# schema.net
KiCad netlist of a schematic drawn in EAGLE
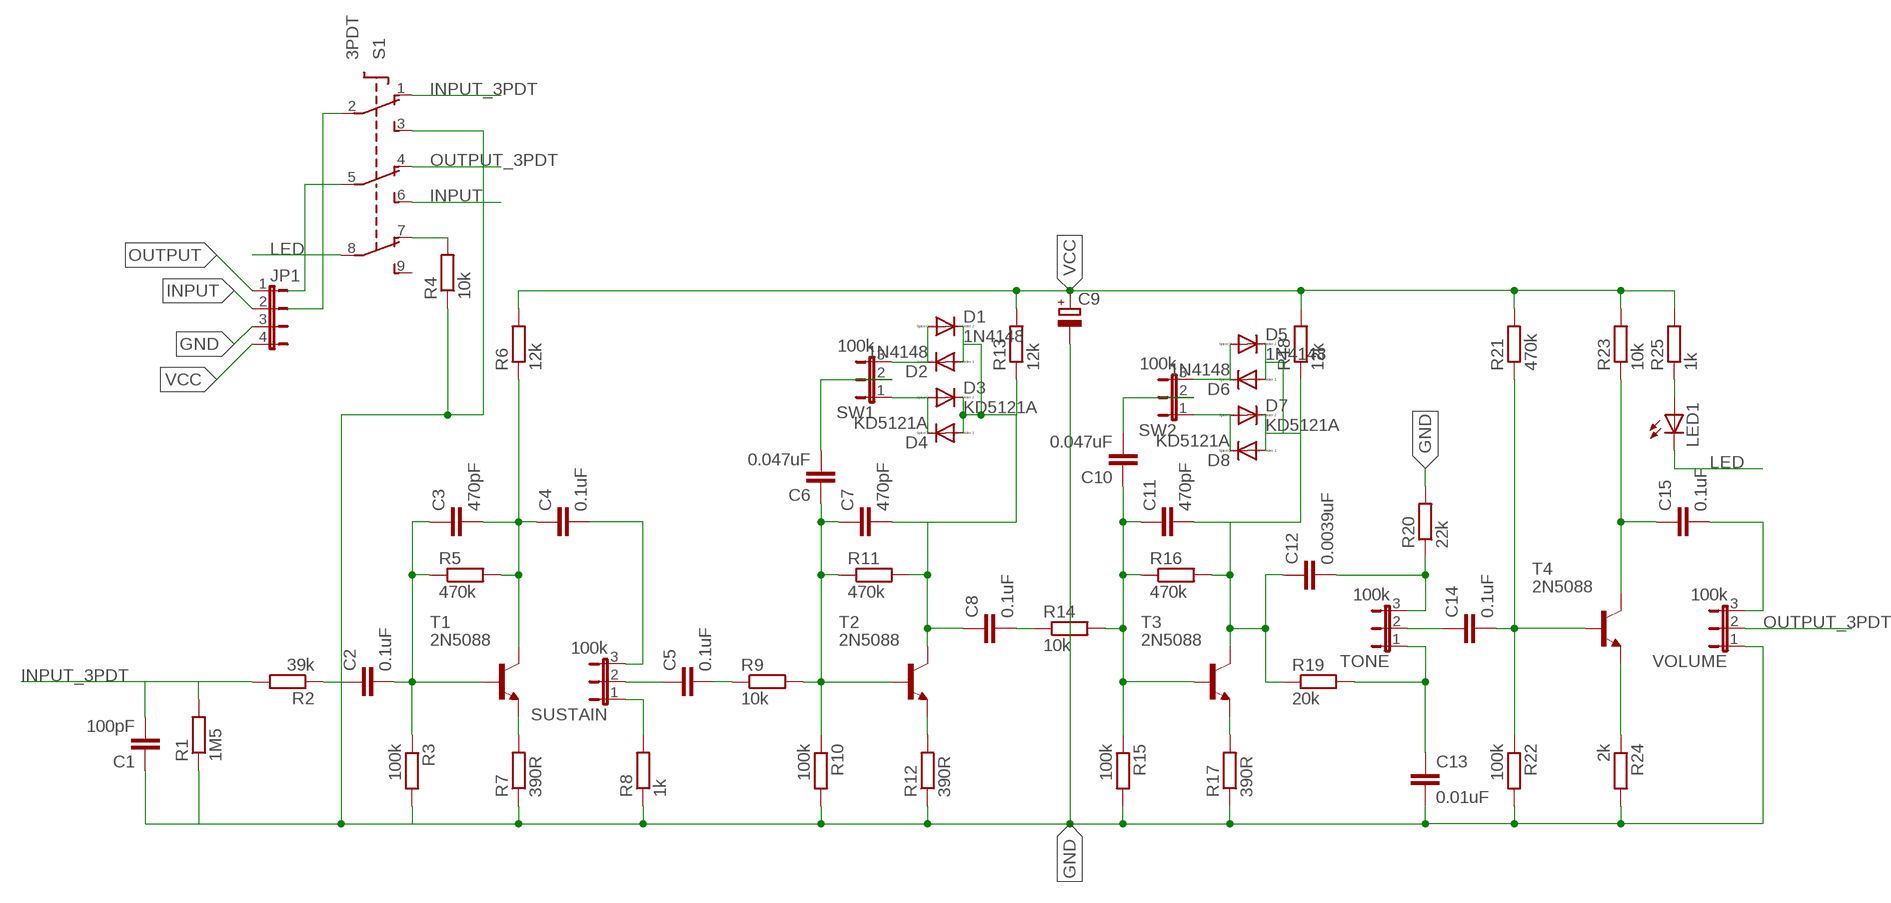
[diagram p0: schematic, sheet 1]

(export (version "E")
  (design (tool "Eeschema 10.0.6"))
  (components
    (comp (ref "C1")
      (value "100pF")
      (footprint "eagle-import:C025-025X050")
      (libsource (lib "eagle-import") (part "C-EU025-025X050"))
    )
    (comp (ref "C2")
      (value "0.1uF")
      (footprint "eagle-import:C075-042X103")
      (libsource (lib "eagle-import") (part "C-EU075-042X103"))
    )
    (comp (ref "C3")
      (value "470pF")
      (footprint "eagle-import:C025-025X050")
      (libsource (lib "eagle-import") (part "C-EU025-025X050"))
    )
    (comp (ref "C4")
      (value "0.1uF")
      (footprint "eagle-import:C075-042X103")
      (libsource (lib "eagle-import") (part "C-EU075-042X103"))
    )
    (comp (ref "C5")
      (value "0.1uF")
      (footprint "eagle-import:C075-042X103")
      (libsource (lib "eagle-import") (part "C-EU075-042X103"))
    )
    (comp (ref "C6")
      (value "0.047uF")
      (footprint "eagle-import:C102-043X133")
      (libsource (lib "eagle-import") (part "C-EU102-043X133"))
    )
    (comp (ref "C7")
      (value "470pF")
      (footprint "eagle-import:C025-025X050")
      (libsource (lib "eagle-import") (part "C-EU025-025X050"))
    )
    (comp (ref "C8")
      (value "0.1uF")
      (footprint "eagle-import:C075-042X103")
      (libsource (lib "eagle-import") (part "C-EU075-042X103"))
    )
    (comp (ref "C9")
      (value "CPOL-EUE2.5-6")
      (footprint "eagle-import:E2,5-6")
      (libsource (lib "eagle-import") (part "CPOL-EUE2.5-6"))
    )
    (comp (ref "C10")
      (value "0.047uF")
      (footprint "eagle-import:C102-043X133")
      (libsource (lib "eagle-import") (part "C-EU102-043X133"))
    )
    (comp (ref "C11")
      (value "470pF")
      (footprint "eagle-import:C025-025X050")
      (libsource (lib "eagle-import") (part "C-EU025-025X050"))
    )
    (comp (ref "C12")
      (value "0.0039uF")
      (footprint "eagle-import:C050-045X075")
      (libsource (lib "eagle-import") (part "C-EU050-045X075"))
    )
    (comp (ref "C13")
      (value "0.01uF")
      (footprint "eagle-import:C075-042X103")
      (libsource (lib "eagle-import") (part "C-EU075-042X103"))
    )
    (comp (ref "C14")
      (value "0.1uF")
      (footprint "eagle-import:C075-042X103")
      (libsource (lib "eagle-import") (part "C-EU075-042X103"))
    )
    (comp (ref "C15")
      (value "0.1uF")
      (footprint "eagle-import:C075-042X103")
      (libsource (lib "eagle-import") (part "C-EU075-042X103"))
    )
    (comp (ref "D1")
      (value "1N4148")
      (footprint "eagle-import:DO35-10")
      (libsource (lib "eagle-import") (part "1N4148DO35-10"))
    )
    (comp (ref "D2")
      (value "1N4148")
      (footprint "eagle-import:DO35-10")
      (libsource (lib "eagle-import") (part "1N4148DO35-10"))
    )
    (comp (ref "D3")
      (value "KD5121A")
      (footprint "eagle-import:DO35-10")
      (libsource (lib "eagle-import") (part "1N4148DO35-10"))
    )
    (comp (ref "D4")
      (value "KD5121A")
      (footprint "eagle-import:DO35-10")
      (libsource (lib "eagle-import") (part "1N4148DO35-10"))
    )
    (comp (ref "D5")
      (value "1N4148")
      (footprint "eagle-import:DO35-10")
      (libsource (lib "eagle-import") (part "1N4148DO35-10"))
    )
    (comp (ref "D6")
      (value "1N4148")
      (footprint "eagle-import:DO35-10")
      (libsource (lib "eagle-import") (part "1N4148DO35-10"))
    )
    (comp (ref "D7")
      (value "KD5121A")
      (footprint "eagle-import:DO35-10")
      (libsource (lib "eagle-import") (part "1N4148DO35-10"))
    )
    (comp (ref "D8")
      (value "KD5121A")
      (footprint "eagle-import:DO35-10")
      (libsource (lib "eagle-import") (part "1N4148DO35-10"))
    )
    (comp (ref "JP1")
      (value "JP4E")
      (footprint "eagle-import:JP4")
      (libsource (lib "eagle-import") (part "JP4E"))
    )
    (comp (ref "LED1")
      (value "LEDB155")
      (footprint "eagle-import:Q62902-B155")
      (libsource (lib "eagle-import") (part "LEDB155"))
    )
    (comp (ref "R1")
      (value "1M5")
      (footprint "eagle-import:0204V")
      (libsource (lib "eagle-import") (part "R-EU_0204/2V"))
    )
    (comp (ref "R2")
      (value "39k")
      (footprint "eagle-import:0204V")
      (libsource (lib "eagle-import") (part "R-EU_0204/2V"))
    )
    (comp (ref "R3")
      (value "100k")
      (footprint "eagle-import:0204V")
      (libsource (lib "eagle-import") (part "R-EU_0204/2V"))
    )
    (comp (ref "R4")
      (value "10k")
      (footprint "eagle-import:0204V")
      (libsource (lib "eagle-import") (part "R-EU_0204/2V"))
    )
    (comp (ref "R5")
      (value "470k")
      (footprint "eagle-import:0204V")
      (libsource (lib "eagle-import") (part "R-EU_0204/2V"))
    )
    (comp (ref "R6")
      (value "12k")
      (footprint "eagle-import:0204V")
      (libsource (lib "eagle-import") (part "R-EU_0204/2V"))
    )
    (comp (ref "R7")
      (value "390R")
      (footprint "eagle-import:0204V")
      (libsource (lib "eagle-import") (part "R-EU_0204/2V"))
    )
    (comp (ref "R8")
      (value "1k")
      (footprint "eagle-import:0204V")
      (libsource (lib "eagle-import") (part "R-EU_0204/2V"))
    )
    (comp (ref "R9")
      (value "10k")
      (footprint "eagle-import:0204V")
      (libsource (lib "eagle-import") (part "R-EU_0204/2V"))
    )
    (comp (ref "R10")
      (value "100k")
      (footprint "eagle-import:0204V")
      (libsource (lib "eagle-import") (part "R-EU_0204/2V"))
    )
    (comp (ref "R11")
      (value "470k")
      (footprint "eagle-import:0204V")
      (libsource (lib "eagle-import") (part "R-EU_0204/2V"))
    )
    (comp (ref "R12")
      (value "390R")
      (footprint "eagle-import:0204V")
      (libsource (lib "eagle-import") (part "R-EU_0204/2V"))
    )
    (comp (ref "R13")
      (value "12k")
      (footprint "eagle-import:0204V")
      (libsource (lib "eagle-import") (part "R-EU_0204/2V"))
    )
    (comp (ref "R14")
      (value "10k")
      (footprint "eagle-import:0204V")
      (libsource (lib "eagle-import") (part "R-EU_0204/2V"))
    )
    (comp (ref "R15")
      (value "100k")
      (footprint "eagle-import:0204V")
      (libsource (lib "eagle-import") (part "R-EU_0204/2V"))
    )
    (comp (ref "R16")
      (value "470k")
      (footprint "eagle-import:0204V")
      (libsource (lib "eagle-import") (part "R-EU_0204/2V"))
    )
    (comp (ref "R17")
      (value "390R")
      (footprint "eagle-import:0204V")
      (libsource (lib "eagle-import") (part "R-EU_0204/2V"))
    )
    (comp (ref "R18")
      (value "12k")
      (footprint "eagle-import:0204V")
      (libsource (lib "eagle-import") (part "R-EU_0204/2V"))
    )
    (comp (ref "R19")
      (value "20k")
      (footprint "eagle-import:0204V")
      (libsource (lib "eagle-import") (part "R-EU_0204/2V"))
    )
    (comp (ref "R20")
      (value "22k")
      (footprint "eagle-import:0204V")
      (libsource (lib "eagle-import") (part "R-EU_0204/2V"))
    )
    (comp (ref "R21")
      (value "470k")
      (footprint "eagle-import:0204V")
      (libsource (lib "eagle-import") (part "R-EU_0204/2V"))
    )
    (comp (ref "R22")
      (value "100k")
      (footprint "eagle-import:0204V")
      (libsource (lib "eagle-import") (part "R-EU_0204/2V"))
    )
    (comp (ref "R23")
      (value "10k")
      (footprint "eagle-import:0204V")
      (libsource (lib "eagle-import") (part "R-EU_0204/2V"))
    )
    (comp (ref "R24")
      (value "2k")
      (footprint "eagle-import:0204V")
      (libsource (lib "eagle-import") (part "R-EU_0204/2V"))
    )
    (comp (ref "R25")
      (value "1k")
      (footprint "eagle-import:0204V")
      (libsource (lib "eagle-import") (part "R-EU_0204/2V"))
    )
    (comp (ref "S1")
      (value "3PDT")
      (footprint "eagle-import:3PDT")
      (libsource (lib "eagle-import") (part "3PDT"))
    )
    (comp (ref "SUSTAIN")
      (value "100k")
      (footprint "eagle-import:JP2")
      (libsource (lib "eagle-import") (part "JP2E"))
    )
    (comp (ref "SW1")
      (value "100k")
      (footprint "eagle-import:JP2")
      (libsource (lib "eagle-import") (part "JP2E"))
    )
    (comp (ref "SW2")
      (value "100k")
      (footprint "eagle-import:JP2")
      (libsource (lib "eagle-import") (part "JP2E"))
    )
    (comp (ref "T1")
      (value "2N5088")
      (footprint "eagle-import:TO92")
      (libsource (lib "eagle-import") (part "2N5088"))
    )
    (comp (ref "T2")
      (value "2N5088")
      (footprint "eagle-import:TO92")
      (libsource (lib "eagle-import") (part "2N5088"))
    )
    (comp (ref "T3")
      (value "2N5088")
      (footprint "eagle-import:TO92")
      (libsource (lib "eagle-import") (part "2N5088"))
    )
    (comp (ref "T4")
      (value "2N5088")
      (footprint "eagle-import:TO92")
      (libsource (lib "eagle-import") (part "2N5088"))
    )
    (comp (ref "TONE")
      (value "100k")
      (footprint "eagle-import:JP2")
      (libsource (lib "eagle-import") (part "JP2E"))
    )
    (comp (ref "VOLUME")
      (value "100k")
      (footprint "eagle-import:JP2")
      (libsource (lib "eagle-import") (part "JP2E"))
    )
  )
  (nets
    (net (code "1") (name "/INPUT_3PDT") (class "Default")
      (node (ref "C1") (pin "2") (pinfunction "2_2") (pintype "passive"))
      (node (ref "R1") (pin "2") (pinfunction "2_2") (pintype "passive"))
      (node (ref "R2") (pin "2") (pinfunction "2_2") (pintype "passive"))
      (node (ref "S1") (pin "1") (pinfunction "O1_1") (pintype "passive"))
    )
    (net (code "2") (name "/LED") (class "Default")
      (node (ref "LED1") (pin "K") (pinfunction "C_K") (pintype "passive"))
      (node (ref "S1") (pin "8") (pinfunction "P3_8") (pintype "passive"))
    )
    (net (code "3") (name "/OUTPUT_3PDT") (class "Default")
      (node (ref "S1") (pin "4") (pinfunction "O2_4") (pintype "passive"))
      (node (ref "VOLUME") (pin "2") (pinfunction "2_2") (pintype "passive"))
    )
    (net (code "4") (name "GND") (class "Default")
      (node (ref "C1") (pin "1") (pinfunction "1_1") (pintype "passive"))
      (node (ref "C13") (pin "2") (pinfunction "2_2") (pintype "passive"))
      (node (ref "C9") (pin "-") (pinfunction "-_-") (pintype "passive"))
      (node (ref "JP1") (pin "3") (pinfunction "3_3") (pintype "passive"))
      (node (ref "R1") (pin "1") (pinfunction "1_1") (pintype "passive"))
      (node (ref "R10") (pin "2") (pinfunction "2_2") (pintype "passive"))
      (node (ref "R12") (pin "1") (pinfunction "1_1") (pintype "passive"))
      (node (ref "R15") (pin "2") (pinfunction "2_2") (pintype "passive"))
      (node (ref "R17") (pin "1") (pinfunction "1_1") (pintype "passive"))
      (node (ref "R20") (pin "2") (pinfunction "2_2") (pintype "passive"))
      (node (ref "R22") (pin "2") (pinfunction "2_2") (pintype "passive"))
      (node (ref "R24") (pin "2") (pinfunction "2_2") (pintype "passive"))
      (node (ref "R3") (pin "2") (pinfunction "2_2") (pintype "passive"))
      (node (ref "R4") (pin "1") (pinfunction "1_1") (pintype "passive"))
      (node (ref "R7") (pin "1") (pinfunction "1_1") (pintype "passive"))
      (node (ref "R8") (pin "1") (pinfunction "1_1") (pintype "passive"))
      (node (ref "S1") (pin "3") (pinfunction "S1_3") (pintype "passive"))
      (node (ref "VOLUME") (pin "1") (pinfunction "1_1") (pintype "passive"))
    )
    (net (code "5") (name "INPUT") (class "Default")
      (node (ref "JP1") (pin "2") (pinfunction "2_2") (pintype "passive"))
      (node (ref "S1") (pin "6") (pinfunction "S2_6") (pintype "passive"))
    )
    (net (code "6") (name "Net-(C2-Pad1)") (class "Default")
      (node (ref "C2") (pin "1") (pinfunction "1_1") (pintype "passive"))
      (node (ref "R2") (pin "1") (pinfunction "1_1") (pintype "passive"))
    )
    (net (code "7") (name "Net-(C4-Pad2)") (class "Default")
      (node (ref "C4") (pin "2") (pinfunction "2_2") (pintype "passive"))
      (node (ref "SUSTAIN") (pin "3") (pinfunction "3_3") (pintype "passive"))
    )
    (net (code "8") (name "Net-(C5-Pad1)") (class "Default")
      (node (ref "C5") (pin "1") (pinfunction "1_1") (pintype "passive"))
      (node (ref "SUSTAIN") (pin "2") (pinfunction "2_2") (pintype "passive"))
    )
    (net (code "9") (name "Net-(C5-Pad2)") (class "Default")
      (node (ref "C5") (pin "2") (pinfunction "2_2") (pintype "passive"))
      (node (ref "R9") (pin "1") (pinfunction "1_1") (pintype "passive"))
    )
    (net (code "10") (name "Net-(C6-Pad2)") (class "Default")
      (node (ref "C6") (pin "2") (pinfunction "2_2") (pintype "passive"))
      (node (ref "SW1") (pin "2") (pinfunction "2_2") (pintype "passive"))
    )
    (net (code "11") (name "Net-(C8-Pad2)") (class "Default")
      (node (ref "C8") (pin "2") (pinfunction "2_2") (pintype "passive"))
      (node (ref "R14") (pin "1") (pinfunction "1_1") (pintype "passive"))
    )
    (net (code "12") (name "Net-(C10-Pad2)") (class "Default")
      (node (ref "C10") (pin "2") (pinfunction "2_2") (pintype "passive"))
      (node (ref "SW2") (pin "2") (pinfunction "2_2") (pintype "passive"))
    )
    (net (code "13") (name "Net-(C12-Pad2)") (class "Default")
      (node (ref "C12") (pin "2") (pinfunction "2_2") (pintype "passive"))
      (node (ref "R20") (pin "1") (pinfunction "1_1") (pintype "passive"))
      (node (ref "TONE") (pin "3") (pinfunction "3_3") (pintype "passive"))
    )
    (net (code "14") (name "Net-(C13-Pad1)") (class "Default")
      (node (ref "C13") (pin "1") (pinfunction "1_1") (pintype "passive"))
      (node (ref "R19") (pin "2") (pinfunction "2_2") (pintype "passive"))
      (node (ref "TONE") (pin "1") (pinfunction "1_1") (pintype "passive"))
    )
    (net (code "15") (name "Net-(C14-Pad1)") (class "Default")
      (node (ref "C14") (pin "1") (pinfunction "1_1") (pintype "passive"))
      (node (ref "TONE") (pin "2") (pinfunction "2_2") (pintype "passive"))
    )
    (net (code "16") (name "Net-(C15-Pad2)") (class "Default")
      (node (ref "C15") (pin "2") (pinfunction "2_2") (pintype "passive"))
      (node (ref "VOLUME") (pin "3") (pinfunction "3_3") (pintype "passive"))
    )
    (net (code "17") (name "Net-(D1-PadA)") (class "Default")
      (node (ref "D1") (pin "A") (pinfunction "A_A") (pintype "passive"))
      (node (ref "D2") (pin "C") (pinfunction "C_C") (pintype "passive"))
      (node (ref "SW1") (pin "3") (pinfunction "3_3") (pintype "passive"))
    )
    (net (code "18") (name "Net-(D3-PadA)") (class "Default")
      (node (ref "D3") (pin "A") (pinfunction "A_A") (pintype "passive"))
      (node (ref "D4") (pin "C") (pinfunction "C_C") (pintype "passive"))
      (node (ref "SW1") (pin "1") (pinfunction "1_1") (pintype "passive"))
    )
    (net (code "19") (name "Net-(D5-PadA)") (class "Default")
      (node (ref "D5") (pin "A") (pinfunction "A_A") (pintype "passive"))
      (node (ref "D6") (pin "C") (pinfunction "C_C") (pintype "passive"))
      (node (ref "SW2") (pin "3") (pinfunction "3_3") (pintype "passive"))
    )
    (net (code "20") (name "Net-(D7-PadA)") (class "Default")
      (node (ref "D7") (pin "A") (pinfunction "A_A") (pintype "passive"))
      (node (ref "D8") (pin "C") (pinfunction "C_C") (pintype "passive"))
      (node (ref "SW2") (pin "1") (pinfunction "1_1") (pintype "passive"))
    )
    (net (code "21") (name "Net-(LED1-PadA)") (class "Default")
      (node (ref "LED1") (pin "A") (pinfunction "A_A") (pintype "passive"))
      (node (ref "R25") (pin "1") (pinfunction "1_1") (pintype "passive"))
    )
    (net (code "22") (name "Net-(R8-Pad2)") (class "Default")
      (node (ref "R8") (pin "2") (pinfunction "2_2") (pintype "passive"))
      (node (ref "SUSTAIN") (pin "1") (pinfunction "1_1") (pintype "passive"))
    )
    (net (code "23") (name "Net-(S1-O3)") (class "Default")
      (node (ref "R4") (pin "2") (pinfunction "2_2") (pintype "passive"))
      (node (ref "S1") (pin "7") (pinfunction "O3_7") (pintype "passive"))
    )
    (net (code "24") (name "Net-(T1-B)") (class "Default")
      (node (ref "C2") (pin "2") (pinfunction "2_2") (pintype "passive"))
      (node (ref "C3") (pin "1") (pinfunction "1_1") (pintype "passive"))
      (node (ref "R3") (pin "1") (pinfunction "1_1") (pintype "passive"))
      (node (ref "R5") (pin "1") (pinfunction "1_1") (pintype "passive"))
      (node (ref "T1") (pin "2") (pinfunction "B_2") (pintype "passive"))
    )
    (net (code "25") (name "Net-(T1-C)") (class "Default")
      (node (ref "C3") (pin "2") (pinfunction "2_2") (pintype "passive"))
      (node (ref "C4") (pin "1") (pinfunction "1_1") (pintype "passive"))
      (node (ref "R5") (pin "2") (pinfunction "2_2") (pintype "passive"))
      (node (ref "R6") (pin "1") (pinfunction "1_1") (pintype "passive"))
      (node (ref "T1") (pin "1") (pinfunction "C_1") (pintype "passive"))
    )
    (net (code "26") (name "Net-(T1-E)") (class "Default")
      (node (ref "R7") (pin "2") (pinfunction "2_2") (pintype "passive"))
      (node (ref "T1") (pin "3") (pinfunction "E_3") (pintype "passive"))
    )
    (net (code "27") (name "Net-(T2-B)") (class "Default")
      (node (ref "C6") (pin "1") (pinfunction "1_1") (pintype "passive"))
      (node (ref "C7") (pin "1") (pinfunction "1_1") (pintype "passive"))
      (node (ref "R10") (pin "1") (pinfunction "1_1") (pintype "passive"))
      (node (ref "R11") (pin "1") (pinfunction "1_1") (pintype "passive"))
      (node (ref "R9") (pin "2") (pinfunction "2_2") (pintype "passive"))
      (node (ref "T2") (pin "2") (pinfunction "B_2") (pintype "passive"))
    )
    (net (code "28") (name "Net-(T2-C)") (class "Default")
      (node (ref "C7") (pin "2") (pinfunction "2_2") (pintype "passive"))
      (node (ref "C8") (pin "1") (pinfunction "1_1") (pintype "passive"))
      (node (ref "D1") (pin "C") (pinfunction "C_C") (pintype "passive"))
      (node (ref "D2") (pin "A") (pinfunction "A_A") (pintype "passive"))
      (node (ref "D3") (pin "C") (pinfunction "C_C") (pintype "passive"))
      (node (ref "D4") (pin "A") (pinfunction "A_A") (pintype "passive"))
      (node (ref "R11") (pin "2") (pinfunction "2_2") (pintype "passive"))
      (node (ref "R13") (pin "1") (pinfunction "1_1") (pintype "passive"))
      (node (ref "T2") (pin "1") (pinfunction "C_1") (pintype "passive"))
    )
    (net (code "29") (name "Net-(T2-E)") (class "Default")
      (node (ref "R12") (pin "2") (pinfunction "2_2") (pintype "passive"))
      (node (ref "T2") (pin "3") (pinfunction "E_3") (pintype "passive"))
    )
    (net (code "30") (name "Net-(T3-B)") (class "Default")
      (node (ref "C10") (pin "1") (pinfunction "1_1") (pintype "passive"))
      (node (ref "C11") (pin "1") (pinfunction "1_1") (pintype "passive"))
      (node (ref "R14") (pin "2") (pinfunction "2_2") (pintype "passive"))
      (node (ref "R15") (pin "1") (pinfunction "1_1") (pintype "passive"))
      (node (ref "R16") (pin "1") (pinfunction "1_1") (pintype "passive"))
      (node (ref "T3") (pin "2") (pinfunction "B_2") (pintype "passive"))
    )
    (net (code "31") (name "Net-(T3-C)") (class "Default")
      (node (ref "C11") (pin "2") (pinfunction "2_2") (pintype "passive"))
      (node (ref "C12") (pin "1") (pinfunction "1_1") (pintype "passive"))
      (node (ref "D5") (pin "C") (pinfunction "C_C") (pintype "passive"))
      (node (ref "D6") (pin "A") (pinfunction "A_A") (pintype "passive"))
      (node (ref "D7") (pin "C") (pinfunction "C_C") (pintype "passive"))
      (node (ref "D8") (pin "A") (pinfunction "A_A") (pintype "passive"))
      (node (ref "R16") (pin "2") (pinfunction "2_2") (pintype "passive"))
      (node (ref "R18") (pin "1") (pinfunction "1_1") (pintype "passive"))
      (node (ref "R19") (pin "1") (pinfunction "1_1") (pintype "passive"))
      (node (ref "T3") (pin "1") (pinfunction "C_1") (pintype "passive"))
    )
    (net (code "32") (name "Net-(T3-E)") (class "Default")
      (node (ref "R17") (pin "2") (pinfunction "2_2") (pintype "passive"))
      (node (ref "T3") (pin "3") (pinfunction "E_3") (pintype "passive"))
    )
    (net (code "33") (name "Net-(T4-B)") (class "Default")
      (node (ref "C14") (pin "2") (pinfunction "2_2") (pintype "passive"))
      (node (ref "R21") (pin "1") (pinfunction "1_1") (pintype "passive"))
      (node (ref "R22") (pin "1") (pinfunction "1_1") (pintype "passive"))
      (node (ref "T4") (pin "2") (pinfunction "B_2") (pintype "passive"))
    )
    (net (code "34") (name "Net-(T4-C)") (class "Default")
      (node (ref "C15") (pin "1") (pinfunction "1_1") (pintype "passive"))
      (node (ref "R23") (pin "1") (pinfunction "1_1") (pintype "passive"))
      (node (ref "T4") (pin "1") (pinfunction "C_1") (pintype "passive"))
    )
    (net (code "35") (name "Net-(T4-E)") (class "Default")
      (node (ref "R24") (pin "1") (pinfunction "1_1") (pintype "passive"))
      (node (ref "T4") (pin "3") (pinfunction "E_3") (pintype "passive"))
    )
    (net (code "36") (name "OUTPUT") (class "Default")
      (node (ref "JP1") (pin "1") (pinfunction "1_1") (pintype "passive"))
    )
    (net (code "37") (name "VCC") (class "Default")
      (node (ref "C9") (pin "+") (pinfunction "+_+") (pintype "passive"))
      (node (ref "JP1") (pin "4") (pinfunction "4_4") (pintype "passive"))
      (node (ref "R13") (pin "2") (pinfunction "2_2") (pintype "passive"))
      (node (ref "R18") (pin "2") (pinfunction "2_2") (pintype "passive"))
      (node (ref "R21") (pin "2") (pinfunction "2_2") (pintype "passive"))
      (node (ref "R23") (pin "2") (pinfunction "2_2") (pintype "passive"))
      (node (ref "R25") (pin "2") (pinfunction "2_2") (pintype "passive"))
      (node (ref "R6") (pin "2") (pinfunction "2_2") (pintype "passive"))
    )
    (net (code "38") (name "unconnected-(S1-P1-Pad2)") (class "Default")
      (node (ref "S1") (pin "2") (pinfunction "P1_2") (pintype "passive"))
    )
    (net (code "39") (name "unconnected-(S1-P2-Pad5)") (class "Default")
      (node (ref "S1") (pin "5") (pinfunction "P2_5") (pintype "passive"))
    )
    (net (code "40") (name "unconnected-(S1-S3-Pad9)") (class "Default")
      (node (ref "S1") (pin "9") (pinfunction "S3_9") (pintype "passive"))
    )
  )
)
